# midi-thru_v1.net
KiCad netlist of a schematic drawn in EAGLE
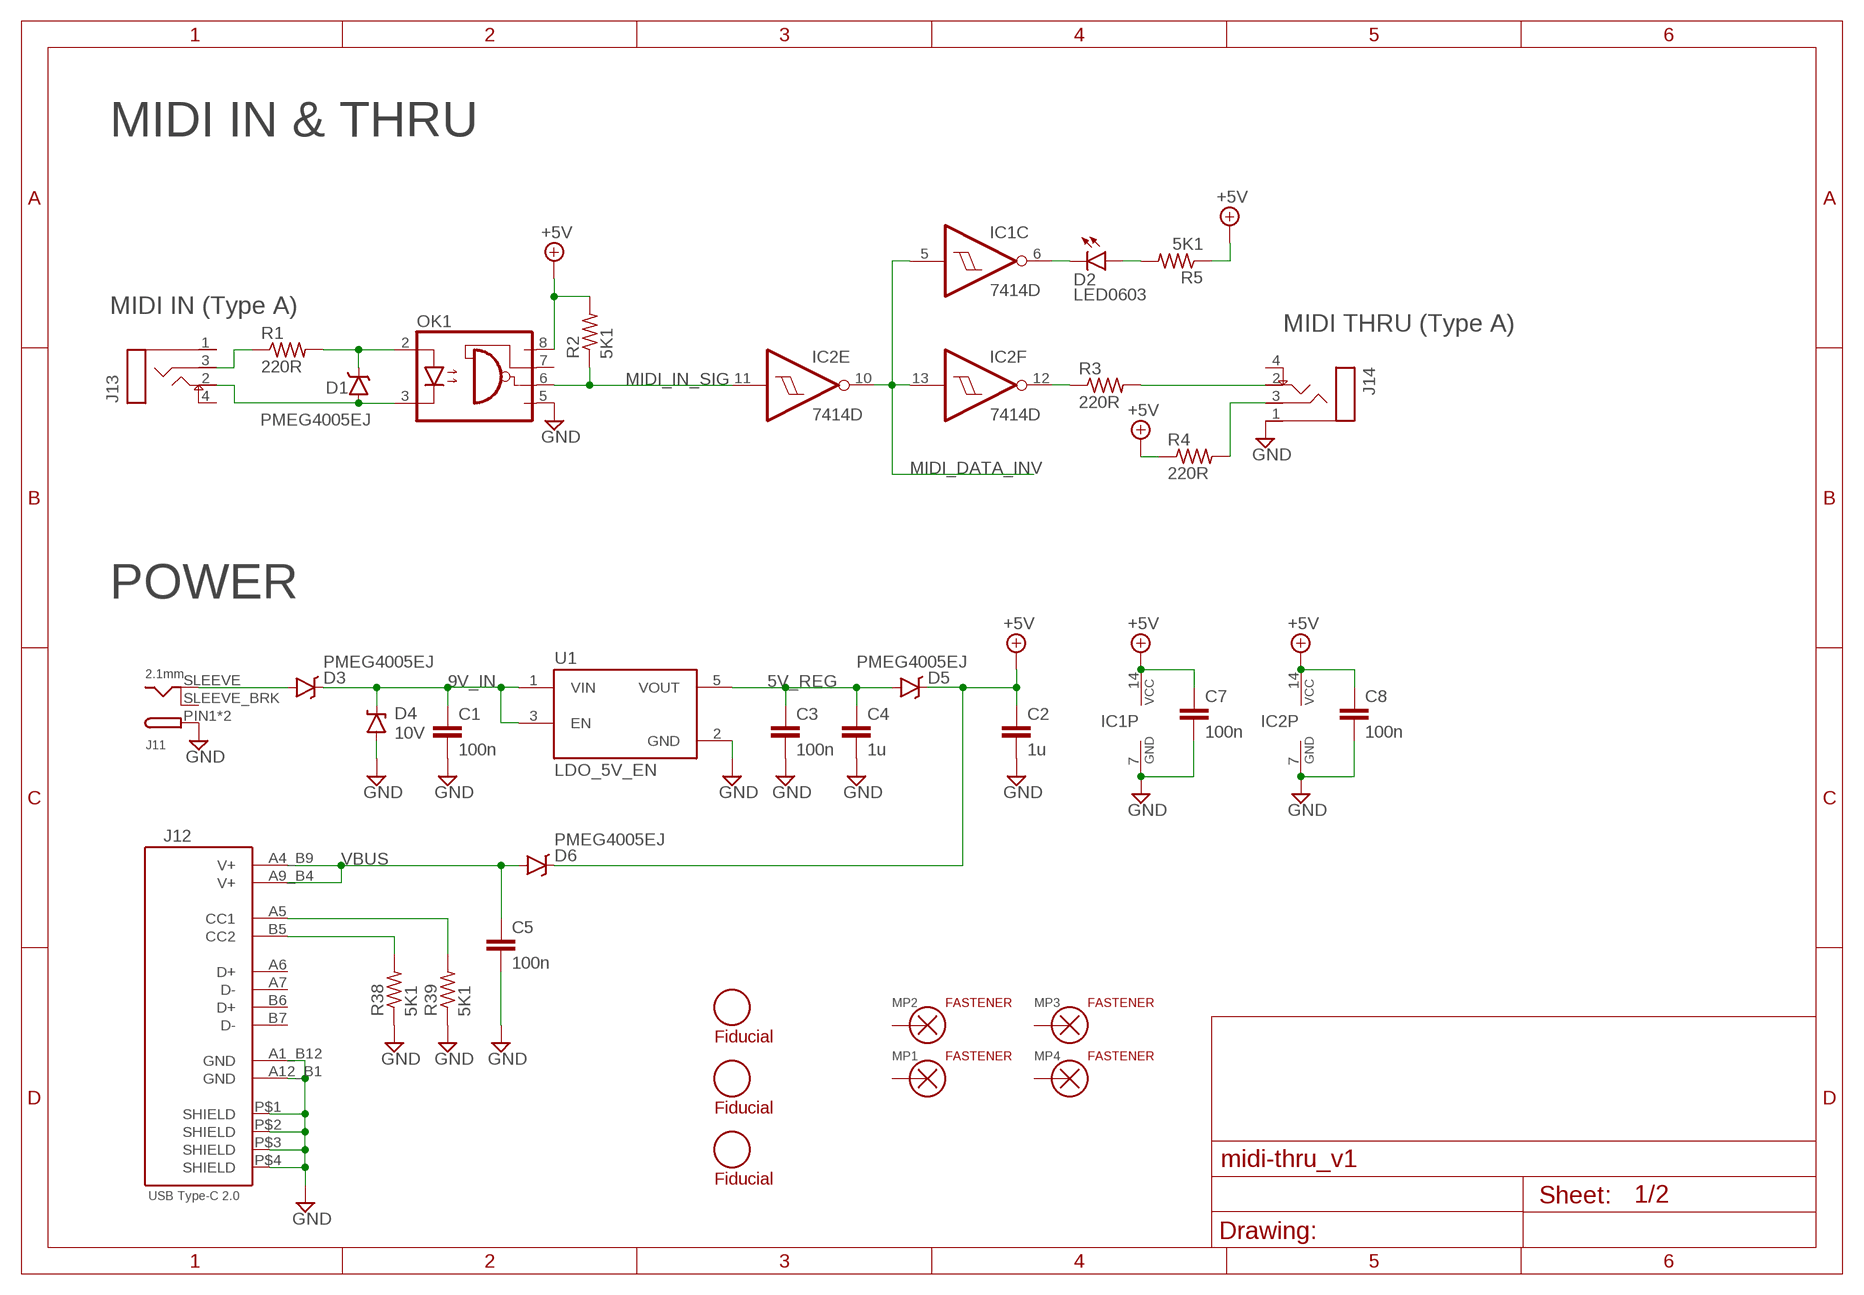
[diagram p0: schematic, sheet 1]
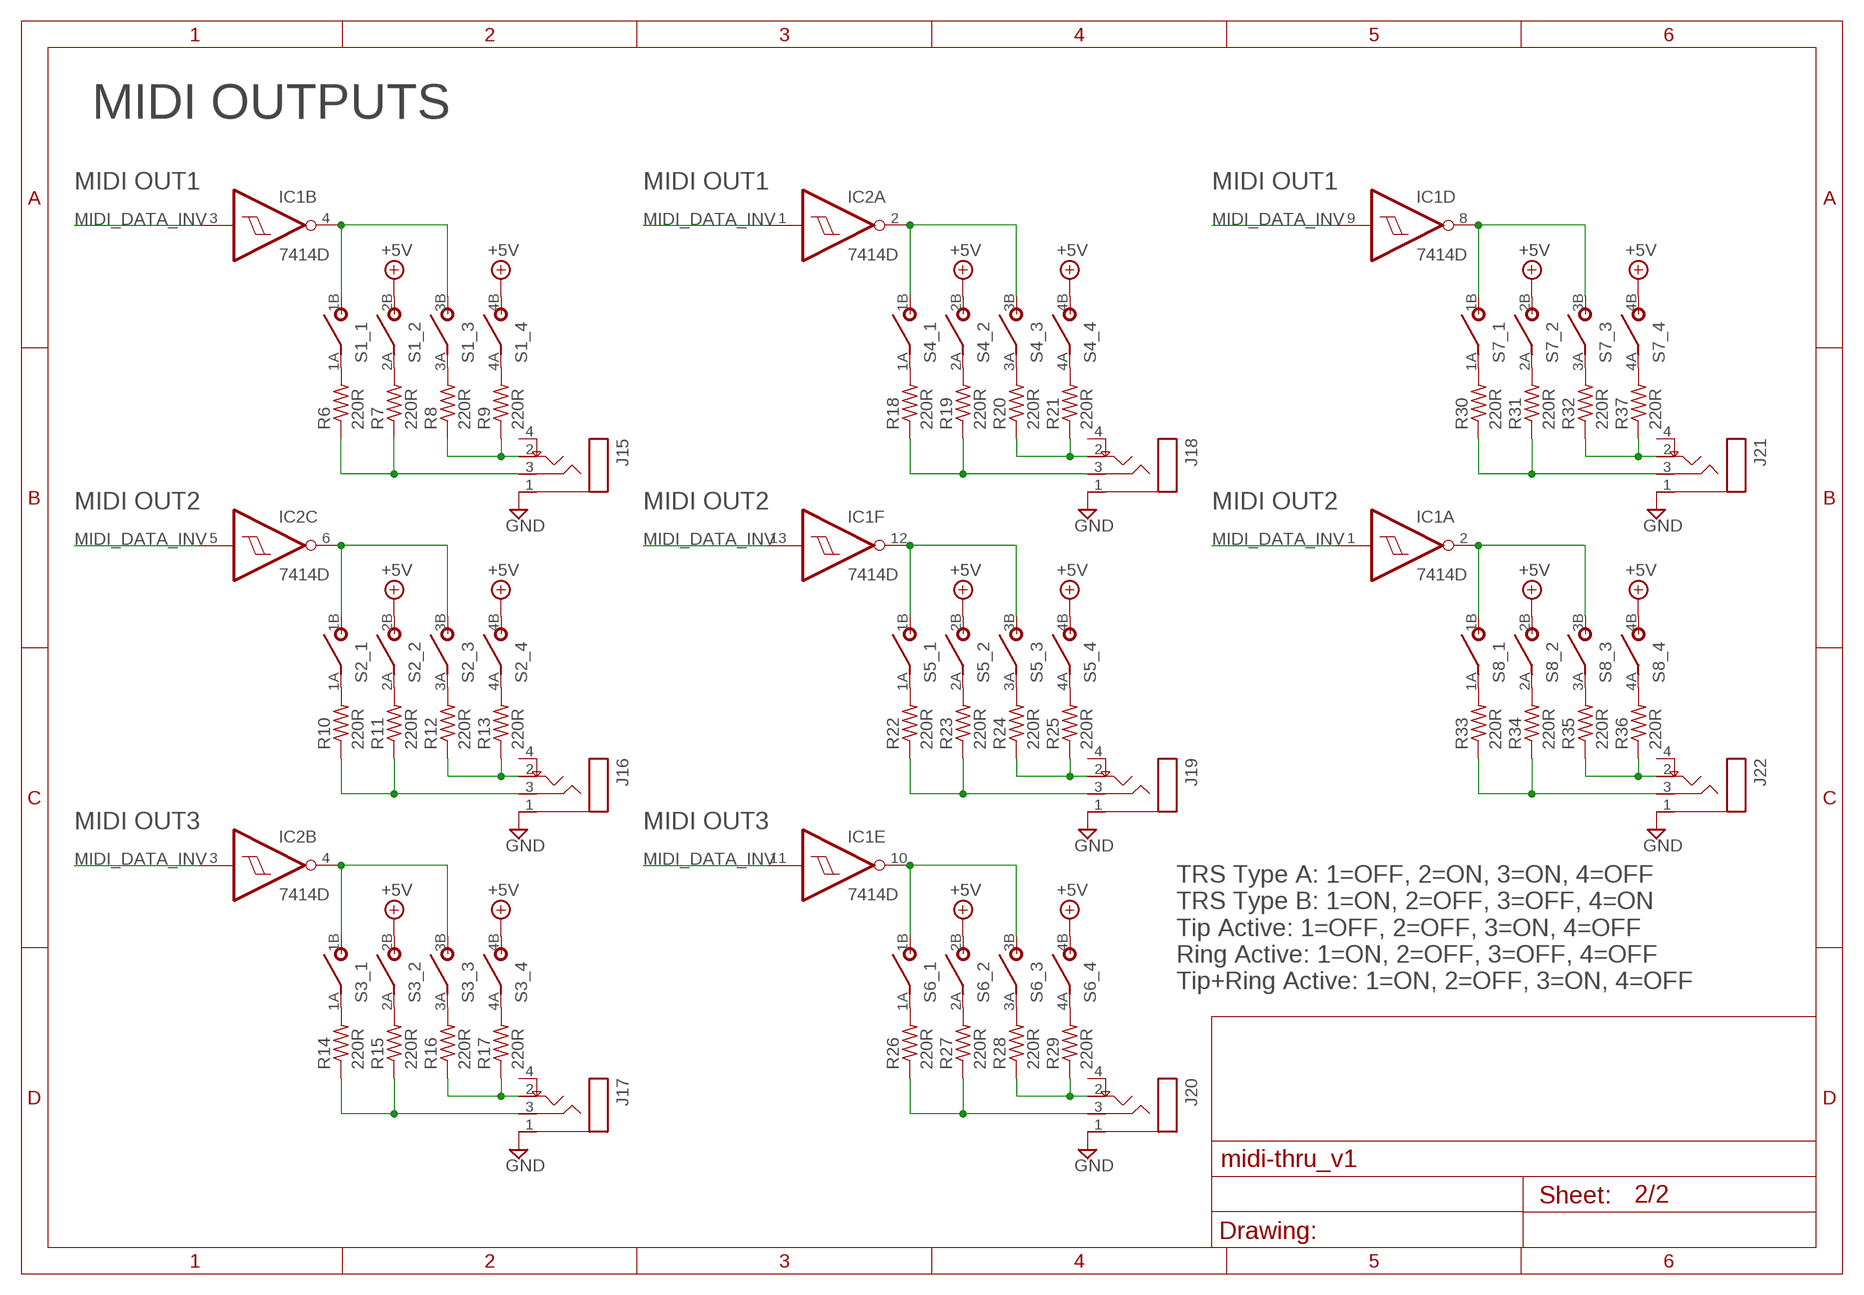
[diagram p1: schematic, sheet 2]

(export (version "E")
  (design (tool "Eeschema 10.0.6"))
  (components
    (comp (ref "IC1")
      (value "7414D")
      (footprint "eagle-import:SO14")
      (fields (field (name "MPN") "74HC14M/TR") (field (name "PART_NO") "74HC14-SOIC-14"))
      (libsource (lib "eagle-import") (part "7414D"))
    )
    (comp (ref "IC2")
      (value "7414D")
      (footprint "eagle-import:SO14")
      (fields (field (name "MPN") "74HC14M/TR") (field (name "PART_NO") "74HC14-SOIC-14"))
      (libsource (lib "eagle-import") (part "7414D"))
    )
    (comp (ref "J15")
      (value "TRS-TIP-SW")
      (footprint "eagle-import:PJ-327C-4A")
      (fields (field (name "MPN") "PJ-327C-4A"))
      (libsource (lib "eagle-import") (part "TRS-TIP-SW3.5MM1"))
    )
    (comp (ref "J16")
      (value "TRS-TIP-SW")
      (footprint "eagle-import:PJ-327C-4A")
      (fields (field (name "MPN") "PJ-327C-4A"))
      (libsource (lib "eagle-import") (part "TRS-TIP-SW3.5MM1"))
    )
    (comp (ref "J17")
      (value "TRS-TIP-SW")
      (footprint "eagle-import:PJ-327C-4A")
      (fields (field (name "MPN") "PJ-327C-4A"))
      (libsource (lib "eagle-import") (part "TRS-TIP-SW3.5MM1"))
    )
    (comp (ref "J18")
      (value "TRS-TIP-SW")
      (footprint "eagle-import:PJ-327C-4A")
      (fields (field (name "MPN") "PJ-327C-4A"))
      (libsource (lib "eagle-import") (part "TRS-TIP-SW3.5MM1"))
    )
    (comp (ref "J19")
      (value "TRS-TIP-SW")
      (footprint "eagle-import:PJ-327C-4A")
      (fields (field (name "MPN") "PJ-327C-4A"))
      (libsource (lib "eagle-import") (part "TRS-TIP-SW3.5MM1"))
    )
    (comp (ref "J20")
      (value "TRS-TIP-SW3.5MM1")
      (footprint "eagle-import:PJ-327C-4A")
      (fields (field (name "MPN") "PJ-327C-4A"))
      (libsource (lib "eagle-import") (part "TRS-TIP-SW3.5MM1"))
    )
    (comp (ref "J21")
      (value "TRS-TIP-SW3.5MM1")
      (footprint "eagle-import:PJ-327C-4A")
      (fields (field (name "MPN") "PJ-327C-4A"))
      (libsource (lib "eagle-import") (part "TRS-TIP-SW3.5MM1"))
    )
    (comp (ref "J22")
      (value "TRS-TIP-SW")
      (footprint "eagle-import:PJ-327C-4A")
      (fields (field (name "MPN") "PJ-327C-4A"))
      (libsource (lib "eagle-import") (part "TRS-TIP-SW3.5MM1"))
    )
    (comp (ref "R6")
      (value "220R")
      (footprint "eagle-import:0603-RES")
      (fields (field (name "MANUFACTURER") "YAGEO") (field (name "PART_NO") "R0603-220R"))
      (libsource (lib "eagle-import") (part "USR0603-220R"))
    )
    (comp (ref "R7")
      (value "220R")
      (footprint "eagle-import:0603-RES")
      (fields (field (name "MANUFACTURER") "YAGEO") (field (name "PART_NO") "R0603-220R"))
      (libsource (lib "eagle-import") (part "USR0603-220R"))
    )
    (comp (ref "R8")
      (value "220R")
      (footprint "eagle-import:0603-RES")
      (fields (field (name "MANUFACTURER") "YAGEO") (field (name "PART_NO") "R0603-220R"))
      (libsource (lib "eagle-import") (part "USR0603-220R"))
    )
    (comp (ref "R9")
      (value "220R")
      (footprint "eagle-import:0603-RES")
      (fields (field (name "MANUFACTURER") "YAGEO") (field (name "PART_NO") "R0603-220R"))
      (libsource (lib "eagle-import") (part "USR0603-220R"))
    )
    (comp (ref "R10")
      (value "220R")
      (footprint "eagle-import:0603-RES")
      (fields (field (name "MANUFACTURER") "YAGEO") (field (name "PART_NO") "R0603-220R"))
      (libsource (lib "eagle-import") (part "USR0603-220R"))
    )
    (comp (ref "R11")
      (value "220R")
      (footprint "eagle-import:0603-RES")
      (fields (field (name "MANUFACTURER") "YAGEO") (field (name "PART_NO") "R0603-220R"))
      (libsource (lib "eagle-import") (part "USR0603-220R"))
    )
    (comp (ref "R12")
      (value "220R")
      (footprint "eagle-import:0603-RES")
      (fields (field (name "MANUFACTURER") "YAGEO") (field (name "PART_NO") "R0603-220R"))
      (libsource (lib "eagle-import") (part "USR0603-220R"))
    )
    (comp (ref "R13")
      (value "220R")
      (footprint "eagle-import:0603-RES")
      (fields (field (name "MANUFACTURER") "YAGEO") (field (name "PART_NO") "R0603-220R"))
      (libsource (lib "eagle-import") (part "USR0603-220R"))
    )
    (comp (ref "R14")
      (value "220R")
      (footprint "eagle-import:0603-RES")
      (fields (field (name "MANUFACTURER") "YAGEO") (field (name "PART_NO") "R0603-220R"))
      (libsource (lib "eagle-import") (part "USR0603-220R"))
    )
    (comp (ref "R15")
      (value "220R")
      (footprint "eagle-import:0603-RES")
      (fields (field (name "MANUFACTURER") "YAGEO") (field (name "PART_NO") "R0603-220R"))
      (libsource (lib "eagle-import") (part "USR0603-220R"))
    )
    (comp (ref "R16")
      (value "220R")
      (footprint "eagle-import:0603-RES")
      (fields (field (name "MANUFACTURER") "YAGEO") (field (name "PART_NO") "R0603-220R"))
      (libsource (lib "eagle-import") (part "USR0603-220R"))
    )
    (comp (ref "R17")
      (value "220R")
      (footprint "eagle-import:0603-RES")
      (fields (field (name "MANUFACTURER") "YAGEO") (field (name "PART_NO") "R0603-220R"))
      (libsource (lib "eagle-import") (part "USR0603-220R"))
    )
    (comp (ref "R18")
      (value "220R")
      (footprint "eagle-import:0603-RES")
      (fields (field (name "MANUFACTURER") "YAGEO") (field (name "PART_NO") "R0603-220R"))
      (libsource (lib "eagle-import") (part "USR0603-220R"))
    )
    (comp (ref "R19")
      (value "220R")
      (footprint "eagle-import:0603-RES")
      (fields (field (name "MANUFACTURER") "YAGEO") (field (name "PART_NO") "R0603-220R"))
      (libsource (lib "eagle-import") (part "USR0603-220R"))
    )
    (comp (ref "R20")
      (value "220R")
      (footprint "eagle-import:0603-RES")
      (fields (field (name "MANUFACTURER") "YAGEO") (field (name "PART_NO") "R0603-220R"))
      (libsource (lib "eagle-import") (part "USR0603-220R"))
    )
    (comp (ref "R21")
      (value "220R")
      (footprint "eagle-import:0603-RES")
      (fields (field (name "MANUFACTURER") "YAGEO") (field (name "PART_NO") "R0603-220R"))
      (libsource (lib "eagle-import") (part "USR0603-220R"))
    )
    (comp (ref "R22")
      (value "220R")
      (footprint "eagle-import:0603-RES")
      (fields (field (name "MANUFACTURER") "YAGEO") (field (name "PART_NO") "R0603-220R"))
      (libsource (lib "eagle-import") (part "USR0603-220R"))
    )
    (comp (ref "R23")
      (value "220R")
      (footprint "eagle-import:0603-RES")
      (fields (field (name "MANUFACTURER") "YAGEO") (field (name "PART_NO") "R0603-220R"))
      (libsource (lib "eagle-import") (part "USR0603-220R"))
    )
    (comp (ref "R24")
      (value "220R")
      (footprint "eagle-import:0603-RES")
      (fields (field (name "MANUFACTURER") "YAGEO") (field (name "PART_NO") "R0603-220R"))
      (libsource (lib "eagle-import") (part "USR0603-220R"))
    )
    (comp (ref "R25")
      (value "220R")
      (footprint "eagle-import:0603-RES")
      (fields (field (name "MANUFACTURER") "YAGEO") (field (name "PART_NO") "R0603-220R"))
      (libsource (lib "eagle-import") (part "USR0603-220R"))
    )
    (comp (ref "R26")
      (value "220R")
      (footprint "eagle-import:0603-RES")
      (fields (field (name "MANUFACTURER") "YAGEO") (field (name "PART_NO") "R0603-220R"))
      (libsource (lib "eagle-import") (part "USR0603-220R"))
    )
    (comp (ref "R27")
      (value "220R")
      (footprint "eagle-import:0603-RES")
      (fields (field (name "MANUFACTURER") "YAGEO") (field (name "PART_NO") "R0603-220R"))
      (libsource (lib "eagle-import") (part "USR0603-220R"))
    )
    (comp (ref "R28")
      (value "220R")
      (footprint "eagle-import:0603-RES")
      (fields (field (name "MANUFACTURER") "YAGEO") (field (name "PART_NO") "R0603-220R"))
      (libsource (lib "eagle-import") (part "USR0603-220R"))
    )
    (comp (ref "R29")
      (value "220R")
      (footprint "eagle-import:0603-RES")
      (fields (field (name "MANUFACTURER") "YAGEO") (field (name "PART_NO") "R0603-220R"))
      (libsource (lib "eagle-import") (part "USR0603-220R"))
    )
    (comp (ref "R30")
      (value "220R")
      (footprint "eagle-import:0603-RES")
      (fields (field (name "MANUFACTURER") "YAGEO") (field (name "PART_NO") "R0603-220R"))
      (libsource (lib "eagle-import") (part "USR0603-220R"))
    )
    (comp (ref "R31")
      (value "220R")
      (footprint "eagle-import:0603-RES")
      (fields (field (name "MANUFACTURER") "YAGEO") (field (name "PART_NO") "R0603-220R"))
      (libsource (lib "eagle-import") (part "USR0603-220R"))
    )
    (comp (ref "R32")
      (value "220R")
      (footprint "eagle-import:0603-RES")
      (fields (field (name "MANUFACTURER") "YAGEO") (field (name "PART_NO") "R0603-220R"))
      (libsource (lib "eagle-import") (part "USR0603-220R"))
    )
    (comp (ref "R33")
      (value "220R")
      (footprint "eagle-import:0603-RES")
      (fields (field (name "MANUFACTURER") "YAGEO") (field (name "PART_NO") "R0603-220R"))
      (libsource (lib "eagle-import") (part "USR0603-220R"))
    )
    (comp (ref "R34")
      (value "220R")
      (footprint "eagle-import:0603-RES")
      (fields (field (name "MANUFACTURER") "YAGEO") (field (name "PART_NO") "R0603-220R"))
      (libsource (lib "eagle-import") (part "USR0603-220R"))
    )
    (comp (ref "R35")
      (value "220R")
      (footprint "eagle-import:0603-RES")
      (fields (field (name "MANUFACTURER") "YAGEO") (field (name "PART_NO") "R0603-220R"))
      (libsource (lib "eagle-import") (part "USR0603-220R"))
    )
    (comp (ref "R36")
      (value "220R")
      (footprint "eagle-import:0603-RES")
      (fields (field (name "MANUFACTURER") "YAGEO") (field (name "PART_NO") "R0603-220R"))
      (libsource (lib "eagle-import") (part "USR0603-220R"))
    )
    (comp (ref "R37")
      (value "220R")
      (footprint "eagle-import:0603-RES")
      (fields (field (name "MANUFACTURER") "YAGEO") (field (name "PART_NO") "R0603-220R"))
      (libsource (lib "eagle-import") (part "USR0603-220R"))
    )
    (comp (ref "S1")
      (value "DIPSW_4SMD")
      (footprint "eagle-import:DIP4_2.54")
      (fields
        (field (name "MANUFACTURER") "CUI")
        (field (name "MPN") "DS04-254-2-04BK-SMT")
        (field (name "PART_NO") "DIP4-2.54-SMD")
      )
      (libsource (lib "eagle-import") (part "DIPSW_4SMD"))
    )
    (comp (ref "S2")
      (value "DIPSW_4SMD")
      (footprint "eagle-import:DIP4_2.54")
      (fields
        (field (name "MANUFACTURER") "CUI")
        (field (name "MPN") "DS04-254-2-04BK-SMT")
        (field (name "PART_NO") "DIP4-2.54-SMD")
      )
      (libsource (lib "eagle-import") (part "DIPSW_4SMD"))
    )
    (comp (ref "S3")
      (value "DIPSW_4SMD")
      (footprint "eagle-import:DIP4_2.54")
      (fields
        (field (name "MANUFACTURER") "CUI")
        (field (name "MPN") "DS04-254-2-04BK-SMT")
        (field (name "PART_NO") "DIP4-2.54-SMD")
      )
      (libsource (lib "eagle-import") (part "DIPSW_4SMD"))
    )
    (comp (ref "S4")
      (value "DIPSW_4SMD")
      (footprint "eagle-import:DIP4_2.54")
      (fields
        (field (name "MANUFACTURER") "CUI")
        (field (name "MPN") "DS04-254-2-04BK-SMT")
        (field (name "PART_NO") "DIP4-2.54-SMD")
      )
      (libsource (lib "eagle-import") (part "DIPSW_4SMD"))
    )
    (comp (ref "S5")
      (value "DIPSW_4SMD")
      (footprint "eagle-import:DIP4_2.54")
      (fields
        (field (name "MANUFACTURER") "CUI")
        (field (name "MPN") "DS04-254-2-04BK-SMT")
        (field (name "PART_NO") "DIP4-2.54-SMD")
      )
      (libsource (lib "eagle-import") (part "DIPSW_4SMD"))
    )
    (comp (ref "S6")
      (value "DIPSW_4SMD")
      (footprint "eagle-import:DIP4_2.54")
      (fields
        (field (name "MANUFACTURER") "CUI")
        (field (name "MPN") "DS04-254-2-04BK-SMT")
        (field (name "PART_NO") "DIP4-2.54-SMD")
      )
      (libsource (lib "eagle-import") (part "DIPSW_4SMD"))
    )
    (comp (ref "S7")
      (value "DIPSW_4SMD")
      (footprint "eagle-import:DIP4_2.54")
      (fields
        (field (name "MANUFACTURER") "CUI")
        (field (name "MPN") "DS04-254-2-04BK-SMT")
        (field (name "PART_NO") "DIP4-2.54-SMD")
      )
      (libsource (lib "eagle-import") (part "DIPSW_4SMD"))
    )
    (comp (ref "S8")
      (value "DIPSW_4SMD")
      (footprint "eagle-import:DIP4_2.54")
      (fields
        (field (name "MANUFACTURER") "CUI")
        (field (name "MPN") "DS04-254-2-04BK-SMT")
        (field (name "PART_NO") "DIP4-2.54-SMD")
      )
      (libsource (lib "eagle-import") (part "DIPSW_4SMD"))
    )
    (comp (ref "C1")
      (value "100n")
      (footprint "eagle-import:0603_CAP")
      (fields
        (field (name "MANUFACTURER") "YAGEO")
        (field (name "PART_NO") "C0603-100NF-50V")
        (field (name "TOLERANCE") "10%")
      )
      (libsource (lib "eagle-import") (part "SMD-NPC0603-100N-50V"))
    )
    (comp (ref "C2")
      (value "1u")
      (footprint "eagle-import:0603_CAP")
      (fields
        (field (name "MANUFACTURER") "YAGEO")
        (field (name "PART_NO") "C0603-1UF-50V")
        (field (name "TOLERANCE") "10%")
      )
      (libsource (lib "eagle-import") (part "SMD-NPC0603-1U-50V"))
    )
    (comp (ref "C3")
      (value "100n")
      (footprint "eagle-import:0603_CAP")
      (fields
        (field (name "MANUFACTURER") "YAGEO")
        (field (name "PART_NO") "C0603-100NF-50V")
        (field (name "TOLERANCE") "10%")
      )
      (libsource (lib "eagle-import") (part "SMD-NPC0603-100N-50V"))
    )
    (comp (ref "C4")
      (value "1u")
      (footprint "eagle-import:0603_CAP")
      (fields
        (field (name "MANUFACTURER") "YAGEO")
        (field (name "PART_NO") "C0603-1UF-50V")
        (field (name "TOLERANCE") "10%")
      )
      (libsource (lib "eagle-import") (part "SMD-NPC0603-1U-50V"))
    )
    (comp (ref "C5")
      (value "100n")
      (footprint "eagle-import:0603_CAP")
      (fields
        (field (name "MANUFACTURER") "YAGEO")
        (field (name "PART_NO") "C0603-100NF-50V")
        (field (name "TOLERANCE") "10%")
      )
      (libsource (lib "eagle-import") (part "SMD-NPC0603-100N-50V"))
    )
    (comp (ref "C7")
      (value "100n")
      (footprint "eagle-import:0603_CAP")
      (fields
        (field (name "MANUFACTURER") "YAGEO")
        (field (name "PART_NO") "C0603-100NF-50V")
        (field (name "TOLERANCE") "10%")
      )
      (libsource (lib "eagle-import") (part "SMD-NPC0603-100N-50V"))
    )
    (comp (ref "C8")
      (value "100n")
      (footprint "eagle-import:0603_CAP")
      (fields
        (field (name "MANUFACTURER") "YAGEO")
        (field (name "PART_NO") "C0603-100NF-50V")
        (field (name "TOLERANCE") "10%")
      )
      (libsource (lib "eagle-import") (part "SMD-NPC0603-100N-50V"))
    )
    (comp (ref "D1")
      (value "PMEG4005EJ")
      (footprint "eagle-import:SOD-323")
      (fields (field (name "PART_NO") "SOD323-SCHOTTKY-1A"))
      (libsource (lib "eagle-import") (part "DIODE-SCHOTTKY-PMEG4005EJ"))
    )
    (comp (ref "D2")
      (value "LED0603")
      (footprint "eagle-import:CHIPLED_0603")
      (fields (field (name "PART_NO") "LED-0603-RED"))
      (libsource (lib "eagle-import") (part "LED0603_R"))
    )
    (comp (ref "D3")
      (value "PMEG4005EJ")
      (footprint "eagle-import:SOD-323")
      (fields (field (name "PART_NO") "SOD323-SCHOTTKY-1A"))
      (libsource (lib "eagle-import") (part "DIODE-SCHOTTKY-PMEG4005EJ"))
    )
    (comp (ref "D4")
      (value "10V")
      (footprint "eagle-import:SOD-323")
      (fields (field (name "PART_NO") "MM3Z10VST1G"))
      (libsource (lib "eagle-import") (part "DIODE-ZENER10V"))
    )
    (comp (ref "D5")
      (value "PMEG4005EJ")
      (footprint "eagle-import:SOD-323")
      (fields (field (name "PART_NO") "SOD323-SCHOTTKY-1A"))
      (libsource (lib "eagle-import") (part "DIODE-SCHOTTKY-PMEG4005EJ"))
    )
    (comp (ref "D6")
      (value "PMEG4005EJ")
      (footprint "eagle-import:SOD-323")
      (fields (field (name "PART_NO") "SOD323-SCHOTTKY-1A"))
      (libsource (lib "eagle-import") (part "DIODE-SCHOTTKY-PMEG4005EJ"))
    )
    (comp (ref "FD1")
      (value "FIDUCIALROUND_1MM")
      (footprint "eagle-import:FIDUCIAL_ROUND_1MM")
      (libsource (lib "eagle-import") (part "FIDUCIALROUND_1MM"))
    )
    (comp (ref "FD2")
      (value "FIDUCIALROUND_1MM")
      (footprint "eagle-import:FIDUCIAL_ROUND_1MM")
      (libsource (lib "eagle-import") (part "FIDUCIALROUND_1MM"))
    )
    (comp (ref "FD3")
      (value "FIDUCIALROUND_1MM")
      (footprint "eagle-import:FIDUCIAL_ROUND_1MM")
      (libsource (lib "eagle-import") (part "FIDUCIALROUND_1MM"))
    )
    (comp (ref "J11")
      (value "2.1mm")
      (footprint "eagle-import:DCJACK_2MM_SMT")
      (fields
        (field (name "MANUFACTURER") "TENSILITY INTERNATIONAL CORP")
        (field (name "MPN") "54-00164")
        (field (name "PART_NO") "DC-2.1-SMD")
      )
      (libsource (lib "eagle-import") (part "DCSMT"))
    )
    (comp (ref "J12")
      (value "USB_TYPE-C_2.0")
      (footprint "eagle-import:12402012E212A")
      (fields
        (field (name "MANUFACTURER") "AMPHENOL")
        (field (name "MPN") "12402012E212A")
        (field (name "PART_NO") "USBC-2.0")
      )
      (libsource (lib "eagle-import") (part "USB_TYPE-C_2.0"))
    )
    (comp (ref "J13")
      (value "TRS-TIP-SW3.5MM1")
      (footprint "eagle-import:PJ-327C-4A")
      (fields (field (name "MPN") "PJ-327C-4A"))
      (libsource (lib "eagle-import") (part "TRS-TIP-SW3.5MM1"))
    )
    (comp (ref "J14")
      (value "TRS-TIP-SW3.5MM1")
      (footprint "eagle-import:PJ-327C-4A")
      (fields (field (name "MPN") "PJ-327C-4A"))
      (libsource (lib "eagle-import") (part "TRS-TIP-SW3.5MM1"))
    )
    (comp (ref "MP1")
      (value "SCREW-FASTENER3")
      (footprint "eagle-import:M3-PANHEAD-VIA")
      (libsource (lib "eagle-import") (part "SCREW-FASTENER3"))
    )
    (comp (ref "MP2")
      (value "SCREW-FASTENER3")
      (footprint "eagle-import:M3-PANHEAD-VIA")
      (libsource (lib "eagle-import") (part "SCREW-FASTENER3"))
    )
    (comp (ref "MP3")
      (value "SCREW-FASTENER3")
      (footprint "eagle-import:M3-PANHEAD-VIA")
      (libsource (lib "eagle-import") (part "SCREW-FASTENER3"))
    )
    (comp (ref "MP4")
      (value "SCREW-FASTENER3")
      (footprint "eagle-import:M3-PANHEAD-VIA")
      (libsource (lib "eagle-import") (part "SCREW-FASTENER3"))
    )
    (comp (ref "OK1")
      (value "6N137")
      (footprint "eagle-import:SMD8")
      (fields
        (field (name "MANUFACTURER") "LITE-ON")
        (field (name "MPN") "6N137S")
        (field (name "PART_NO") "6N137-SMD")
      )
      (libsource (lib "eagle-import") (part "6N137S"))
    )
    (comp (ref "R1")
      (value "220R")
      (footprint "eagle-import:0603-RES")
      (fields (field (name "MANUFACTURER") "YAGEO") (field (name "PART_NO") "R0603-220R"))
      (libsource (lib "eagle-import") (part "USR0603-220R"))
    )
    (comp (ref "R2")
      (value "5K1")
      (footprint "eagle-import:0603-RES")
      (fields (field (name "MANUFACTURER") "YAGEO") (field (name "PART_NO") "R0603-5K1"))
      (libsource (lib "eagle-import") (part "USR0603-5K1"))
    )
    (comp (ref "R3")
      (value "220R")
      (footprint "eagle-import:0603-RES")
      (fields (field (name "MANUFACTURER") "YAGEO") (field (name "PART_NO") "R0603-220R"))
      (libsource (lib "eagle-import") (part "USR0603-220R"))
    )
    (comp (ref "R4")
      (value "220R")
      (footprint "eagle-import:0603-RES")
      (fields (field (name "MANUFACTURER") "YAGEO") (field (name "PART_NO") "R0603-220R"))
      (libsource (lib "eagle-import") (part "USR0603-220R"))
    )
    (comp (ref "R5")
      (value "5K1")
      (footprint "eagle-import:0603-RES")
      (fields (field (name "MANUFACTURER") "YAGEO") (field (name "PART_NO") "R0603-5K1"))
      (libsource (lib "eagle-import") (part "USR0603-5K1"))
    )
    (comp (ref "R38")
      (value "5K1")
      (footprint "eagle-import:0603-RES")
      (fields (field (name "MANUFACTURER") "YAGEO") (field (name "PART_NO") "R0603-5K1"))
      (libsource (lib "eagle-import") (part "USR0603-5K1"))
    )
    (comp (ref "R39")
      (value "5K1")
      (footprint "eagle-import:0603-RES")
      (fields (field (name "MANUFACTURER") "YAGEO") (field (name "PART_NO") "R0603-5K1"))
      (libsource (lib "eagle-import") (part "USR0603-5K1"))
    )
    (comp (ref "U1")
      (value "LDO_5V_EN")
      (footprint "eagle-import:SOT23-5")
      (fields (field (name "MPN") "SPX5205M5-L-5-0/TR") (field (name "PART_NO") "LDO-SOT23-5V"))
      (libsource (lib "eagle-import") (part "LDO_5V_EN"))
    )
  )
  (nets
    (net (code "1") (name "+5V") (class "Default")
      (node (ref "C2") (pin "1") (pinfunction "1_1") (pintype "passive"))
      (node (ref "C7") (pin "1") (pinfunction "1_1") (pintype "passive"))
      (node (ref "C8") (pin "1") (pinfunction "1_1") (pintype "passive"))
      (node (ref "D5") (pin "C") (pinfunction "C_C") (pintype "passive"))
      (node (ref "D6") (pin "C") (pinfunction "C_C") (pintype "passive"))
      (node (ref "IC1") (pin "14") (pinfunction "VCC_14") (pintype "power_in"))
      (node (ref "IC2") (pin "14") (pinfunction "VCC_14") (pintype "power_in"))
      (node (ref "OK1") (pin "8") (pinfunction "VCC_8") (pintype "passive"))
      (node (ref "R2") (pin "2") (pinfunction "2_2") (pintype "passive"))
      (node (ref "R4") (pin "1") (pinfunction "1_1") (pintype "passive"))
      (node (ref "R5") (pin "1") (pinfunction "1_1") (pintype "passive"))
      (node (ref "S1") (pin "2B") (pinfunction "S_2B") (pintype "passive"))
      (node (ref "S1") (pin "4B") (pinfunction "S_4B") (pintype "passive"))
      (node (ref "S2") (pin "2B") (pinfunction "S_2B") (pintype "passive"))
      (node (ref "S2") (pin "4B") (pinfunction "S_4B") (pintype "passive"))
      (node (ref "S3") (pin "2B") (pinfunction "S_2B") (pintype "passive"))
      (node (ref "S3") (pin "4B") (pinfunction "S_4B") (pintype "passive"))
      (node (ref "S4") (pin "2B") (pinfunction "S_2B") (pintype "passive"))
      (node (ref "S4") (pin "4B") (pinfunction "S_4B") (pintype "passive"))
      (node (ref "S5") (pin "2B") (pinfunction "S_2B") (pintype "passive"))
      (node (ref "S5") (pin "4B") (pinfunction "S_4B") (pintype "passive"))
      (node (ref "S6") (pin "2B") (pinfunction "S_2B") (pintype "passive"))
      (node (ref "S6") (pin "4B") (pinfunction "S_4B") (pintype "passive"))
      (node (ref "S7") (pin "2B") (pinfunction "S_2B") (pintype "passive"))
      (node (ref "S7") (pin "4B") (pinfunction "S_4B") (pintype "passive"))
      (node (ref "S8") (pin "2B") (pinfunction "S_2B") (pintype "passive"))
      (node (ref "S8") (pin "4B") (pinfunction "S_4B") (pintype "passive"))
    )
    (net (code "2") (name "5V_REG") (class "Default")
      (node (ref "C3") (pin "1") (pinfunction "1_1") (pintype "passive"))
      (node (ref "C4") (pin "1") (pinfunction "1_1") (pintype "passive"))
      (node (ref "D5") (pin "A") (pinfunction "A_A") (pintype "passive"))
      (node (ref "U1") (pin "5") (pinfunction "VOUT_5") (pintype "output"))
    )
    (net (code "3") (name "9V_IN") (class "Default")
      (node (ref "C1") (pin "1") (pinfunction "1_1") (pintype "passive"))
      (node (ref "D3") (pin "C") (pinfunction "C_C") (pintype "passive"))
      (node (ref "D4") (pin "C") (pinfunction "C_C") (pintype "passive"))
      (node (ref "U1") (pin "1") (pinfunction "VIN_1") (pintype "input"))
      (node (ref "U1") (pin "3") (pinfunction "EN_3") (pintype "input"))
    )
    (net (code "4") (name "CONNECT") (class "Default")
      (node (ref "J11") (pin "SLEEVE_BRK") (pinfunction "CONNECT_SLEEVE_BRK") (pintype "power_in"))
    )
    (net (code "5") (name "GND") (class "Default")
      (node (ref "C1") (pin "2") (pinfunction "2_2") (pintype "passive"))
      (node (ref "C2") (pin "2") (pinfunction "2_2") (pintype "passive"))
      (node (ref "C3") (pin "2") (pinfunction "2_2") (pintype "passive"))
      (node (ref "C4") (pin "2") (pinfunction "2_2") (pintype "passive"))
      (node (ref "C5") (pin "2") (pinfunction "2_2") (pintype "passive"))
      (node (ref "C7") (pin "2") (pinfunction "2_2") (pintype "passive"))
      (node (ref "C8") (pin "2") (pinfunction "2_2") (pintype "passive"))
      (node (ref "D4") (pin "A") (pinfunction "A_A") (pintype "passive"))
      (node (ref "IC1") (pin "7") (pinfunction "GND_7") (pintype "power_in"))
      (node (ref "IC2") (pin "7") (pinfunction "GND_7") (pintype "power_in"))
      (node (ref "J11") (pin "PIN1") (pinfunction "PIN_PIN1") (pintype "power_in"))
      (node (ref "J11") (pin "PIN2") (pinfunction "PIN_PIN2") (pintype "power_in"))
      (node (ref "J12") (pin "A12_B1") (pinfunction "GND_A12_B1") (pintype "power_in"))
      (node (ref "J12") (pin "A1_B12") (pinfunction "GND_A1_B12") (pintype "power_in"))
      (node (ref "J12") (pin "P$1") (pinfunction "SHIELD_P$1") (pintype "bidirectional"))
      (node (ref "J12") (pin "P$2") (pinfunction "SHIELD_P$2") (pintype "bidirectional"))
      (node (ref "J12") (pin "P$3") (pinfunction "SHIELD_P$3") (pintype "bidirectional"))
      (node (ref "J12") (pin "P$4") (pinfunction "SHIELD_P$4") (pintype "bidirectional"))
      (node (ref "J14") (pin "1") (pinfunction "S_1") (pintype "passive"))
      (node (ref "J15") (pin "1") (pinfunction "S_1") (pintype "passive"))
      (node (ref "J16") (pin "1") (pinfunction "S_1") (pintype "passive"))
      (node (ref "J17") (pin "1") (pinfunction "S_1") (pintype "passive"))
      (node (ref "J18") (pin "1") (pinfunction "S_1") (pintype "passive"))
      (node (ref "J19") (pin "1") (pinfunction "S_1") (pintype "passive"))
      (node (ref "J20") (pin "1") (pinfunction "S_1") (pintype "passive"))
      (node (ref "J21") (pin "1") (pinfunction "S_1") (pintype "passive"))
      (node (ref "J22") (pin "1") (pinfunction "S_1") (pintype "passive"))
      (node (ref "OK1") (pin "5") (pinfunction "GND_5") (pintype "passive"))
      (node (ref "R38") (pin "1") (pinfunction "1_1") (pintype "passive"))
      (node (ref "R39") (pin "1") (pinfunction "1_1") (pintype "passive"))
      (node (ref "U1") (pin "2") (pinfunction "GND_2") (pintype "power_in"))
    )
    (net (code "6") (name "MIDI_DATA_INV") (class "Default")
      (node (ref "IC1") (pin "1") (pinfunction "I_1") (pintype "input"))
      (node (ref "IC1") (pin "11") (pinfunction "I_11") (pintype "input"))
      (node (ref "IC1") (pin "13") (pinfunction "I_13") (pintype "input"))
      (node (ref "IC1") (pin "3") (pinfunction "I_3") (pintype "input"))
      (node (ref "IC1") (pin "5") (pinfunction "I_5") (pintype "input"))
      (node (ref "IC1") (pin "9") (pinfunction "I_9") (pintype "input"))
      (node (ref "IC2") (pin "1") (pinfunction "I_1") (pintype "input"))
      (node (ref "IC2") (pin "10") (pinfunction "O_10") (pintype "output"))
      (node (ref "IC2") (pin "13") (pinfunction "I_13") (pintype "input"))
      (node (ref "IC2") (pin "3") (pinfunction "I_3") (pintype "input"))
      (node (ref "IC2") (pin "5") (pinfunction "I_5") (pintype "input"))
    )
    (net (code "7") (name "MIDI_IN_SIG") (class "Default")
      (node (ref "IC2") (pin "11") (pinfunction "I_11") (pintype "input"))
      (node (ref "OK1") (pin "6") (pinfunction "VO_6") (pintype "passive"))
      (node (ref "R2") (pin "1") (pinfunction "1_1") (pintype "passive"))
    )
    (net (code "8") (name "Net-(D2-PadA)") (class "Default")
      (node (ref "D2") (pin "A") (pinfunction "A_A") (pintype "passive"))
      (node (ref "R5") (pin "2") (pinfunction "2_2") (pintype "passive"))
    )
    (net (code "9") (name "Net-(D3-PadA)") (class "Default")
      (node (ref "D3") (pin "A") (pinfunction "A_A") (pintype "passive"))
      (node (ref "J11") (pin "SLEEVE") (pinfunction "SLEEVE_SLEEVE") (pintype "power_in"))
    )
    (net (code "10") (name "Net-(IC1A-O)") (class "Default")
      (node (ref "IC1") (pin "2") (pinfunction "O_2") (pintype "output"))
      (node (ref "S8") (pin "1B") (pinfunction "S_1B") (pintype "passive"))
      (node (ref "S8") (pin "3B") (pinfunction "S_3B") (pintype "passive"))
    )
    (net (code "11") (name "Net-(IC1B-O)") (class "Default")
      (node (ref "IC1") (pin "4") (pinfunction "O_4") (pintype "output"))
      (node (ref "S1") (pin "1B") (pinfunction "S_1B") (pintype "passive"))
      (node (ref "S1") (pin "3B") (pinfunction "S_3B") (pintype "passive"))
    )
    (net (code "12") (name "Net-(IC1C-O)") (class "Default")
      (node (ref "D2") (pin "C") (pinfunction "C_C") (pintype "passive"))
      (node (ref "IC1") (pin "6") (pinfunction "O_6") (pintype "output"))
    )
    (net (code "13") (name "Net-(IC1D-O)") (class "Default")
      (node (ref "IC1") (pin "8") (pinfunction "O_8") (pintype "output"))
      (node (ref "S7") (pin "1B") (pinfunction "S_1B") (pintype "passive"))
      (node (ref "S7") (pin "3B") (pinfunction "S_3B") (pintype "passive"))
    )
    (net (code "14") (name "Net-(IC1E-O)") (class "Default")
      (node (ref "IC1") (pin "10") (pinfunction "O_10") (pintype "output"))
      (node (ref "S6") (pin "1B") (pinfunction "S_1B") (pintype "passive"))
      (node (ref "S6") (pin "3B") (pinfunction "S_3B") (pintype "passive"))
    )
    (net (code "15") (name "Net-(IC1F-O)") (class "Default")
      (node (ref "IC1") (pin "12") (pinfunction "O_12") (pintype "output"))
      (node (ref "S5") (pin "1B") (pinfunction "S_1B") (pintype "passive"))
      (node (ref "S5") (pin "3B") (pinfunction "S_3B") (pintype "passive"))
    )
    (net (code "16") (name "Net-(IC2A-O)") (class "Default")
      (node (ref "IC2") (pin "2") (pinfunction "O_2") (pintype "output"))
      (node (ref "S4") (pin "1B") (pinfunction "S_1B") (pintype "passive"))
      (node (ref "S4") (pin "3B") (pinfunction "S_3B") (pintype "passive"))
    )
    (net (code "17") (name "Net-(IC2B-O)") (class "Default")
      (node (ref "IC2") (pin "4") (pinfunction "O_4") (pintype "output"))
      (node (ref "S3") (pin "1B") (pinfunction "S_1B") (pintype "passive"))
      (node (ref "S3") (pin "3B") (pinfunction "S_3B") (pintype "passive"))
    )
    (net (code "18") (name "Net-(IC2C-O)") (class "Default")
      (node (ref "IC2") (pin "6") (pinfunction "O_6") (pintype "output"))
      (node (ref "S2") (pin "1B") (pinfunction "S_1B") (pintype "passive"))
      (node (ref "S2") (pin "3B") (pinfunction "S_3B") (pintype "passive"))
    )
    (net (code "19") (name "Net-(IC2F-O)") (class "Default")
      (node (ref "IC2") (pin "12") (pinfunction "O_12") (pintype "output"))
      (node (ref "R3") (pin "1") (pinfunction "1_1") (pintype "passive"))
    )
    (net (code "20") (name "Net-(J12-CC1)") (class "Default")
      (node (ref "J12") (pin "A5") (pinfunction "CC1_A5") (pintype "bidirectional"))
      (node (ref "R39") (pin "2") (pinfunction "2_2") (pintype "passive"))
    )
    (net (code "21") (name "Net-(J12-CC2)") (class "Default")
      (node (ref "J12") (pin "B5") (pinfunction "CC2_B5") (pintype "bidirectional"))
      (node (ref "R38") (pin "2") (pinfunction "2_2") (pintype "passive"))
    )
    (net (code "22") (name "Net-(J13-R)") (class "Default")
      (node (ref "J13") (pin "3") (pinfunction "R_3") (pintype "passive"))
      (node (ref "R1") (pin "1") (pinfunction "1_1") (pintype "passive"))
    )
    (net (code "23") (name "Net-(J13-T)") (class "Default")
      (node (ref "D1") (pin "A") (pinfunction "A_A") (pintype "passive"))
      (node (ref "J13") (pin "2") (pinfunction "T_2") (pintype "passive"))
      (node (ref "OK1") (pin "3") (pinfunction "C_3") (pintype "passive"))
    )
    (net (code "24") (name "Net-(J14-R)") (class "Default")
      (node (ref "J14") (pin "3") (pinfunction "R_3") (pintype "passive"))
      (node (ref "R4") (pin "2") (pinfunction "2_2") (pintype "passive"))
    )
    (net (code "25") (name "Net-(J14-T)") (class "Default")
      (node (ref "J14") (pin "2") (pinfunction "T_2") (pintype "passive"))
      (node (ref "R3") (pin "2") (pinfunction "2_2") (pintype "passive"))
    )
    (net (code "26") (name "Net-(J15-R)") (class "Default")
      (node (ref "J15") (pin "3") (pinfunction "R_3") (pintype "passive"))
      (node (ref "R6") (pin "1") (pinfunction "1_1") (pintype "passive"))
      (node (ref "R7") (pin "1") (pinfunction "1_1") (pintype "passive"))
    )
    (net (code "27") (name "Net-(J15-T)") (class "Default")
      (node (ref "J15") (pin "2") (pinfunction "T_2") (pintype "passive"))
      (node (ref "R8") (pin "1") (pinfunction "1_1") (pintype "passive"))
      (node (ref "R9") (pin "1") (pinfunction "1_1") (pintype "passive"))
    )
    (net (code "28") (name "Net-(J16-R)") (class "Default")
      (node (ref "J16") (pin "3") (pinfunction "R_3") (pintype "passive"))
      (node (ref "R10") (pin "1") (pinfunction "1_1") (pintype "passive"))
      (node (ref "R11") (pin "1") (pinfunction "1_1") (pintype "passive"))
    )
    (net (code "29") (name "Net-(J16-T)") (class "Default")
      (node (ref "J16") (pin "2") (pinfunction "T_2") (pintype "passive"))
      (node (ref "R12") (pin "1") (pinfunction "1_1") (pintype "passive"))
      (node (ref "R13") (pin "1") (pinfunction "1_1") (pintype "passive"))
    )
    (net (code "30") (name "Net-(J17-R)") (class "Default")
      (node (ref "J17") (pin "3") (pinfunction "R_3") (pintype "passive"))
      (node (ref "R14") (pin "1") (pinfunction "1_1") (pintype "passive"))
      (node (ref "R15") (pin "1") (pinfunction "1_1") (pintype "passive"))
    )
    (net (code "31") (name "Net-(J17-T)") (class "Default")
      (node (ref "J17") (pin "2") (pinfunction "T_2") (pintype "passive"))
      (node (ref "R16") (pin "1") (pinfunction "1_1") (pintype "passive"))
      (node (ref "R17") (pin "1") (pinfunction "1_1") (pintype "passive"))
    )
    (net (code "32") (name "Net-(J18-R)") (class "Default")
      (node (ref "J18") (pin "3") (pinfunction "R_3") (pintype "passive"))
      (node (ref "R18") (pin "1") (pinfunction "1_1") (pintype "passive"))
      (node (ref "R19") (pin "1") (pinfunction "1_1") (pintype "passive"))
    )
    (net (code "33") (name "Net-(J18-T)") (class "Default")
      (node (ref "J18") (pin "2") (pinfunction "T_2") (pintype "passive"))
      (node (ref "R20") (pin "1") (pinfunction "1_1") (pintype "passive"))
      (node (ref "R21") (pin "1") (pinfunction "1_1") (pintype "passive"))
    )
    (net (code "34") (name "Net-(J19-R)") (class "Default")
      (node (ref "J19") (pin "3") (pinfunction "R_3") (pintype "passive"))
      (node (ref "R22") (pin "1") (pinfunction "1_1") (pintype "passive"))
      (node (ref "R23") (pin "1") (pinfunction "1_1") (pintype "passive"))
    )
    (net (code "35") (name "Net-(J19-T)") (class "Default")
      (node (ref "J19") (pin "2") (pinfunction "T_2") (pintype "passive"))
      (node (ref "R24") (pin "1") (pinfunction "1_1") (pintype "passive"))
      (node (ref "R25") (pin "1") (pinfunction "1_1") (pintype "passive"))
    )
    (net (code "36") (name "Net-(J20-R)") (class "Default")
      (node (ref "J20") (pin "3") (pinfunction "R_3") (pintype "passive"))
      (node (ref "R26") (pin "1") (pinfunction "1_1") (pintype "passive"))
      (node (ref "R27") (pin "1") (pinfunction "1_1") (pintype "passive"))
    )
    (net (code "37") (name "Net-(J20-T)") (class "Default")
      (node (ref "J20") (pin "2") (pinfunction "T_2") (pintype "passive"))
      (node (ref "R28") (pin "1") (pinfunction "1_1") (pintype "passive"))
      (node (ref "R29") (pin "1") (pinfunction "1_1") (pintype "passive"))
    )
    (net (code "38") (name "Net-(J21-R)") (class "Default")
      (node (ref "J21") (pin "3") (pinfunction "R_3") (pintype "passive"))
      (node (ref "R30") (pin "1") (pinfunction "1_1") (pintype "passive"))
      (node (ref "R31") (pin "1") (pinfunction "1_1") (pintype "passive"))
    )
    (net (code "39") (name "Net-(J21-T)") (class "Default")
      (node (ref "J21") (pin "2") (pinfunction "T_2") (pintype "passive"))
      (node (ref "R32") (pin "1") (pinfunction "1_1") (pintype "passive"))
      (node (ref "R37") (pin "1") (pinfunction "1_1") (pintype "passive"))
    )
    (net (code "40") (name "Net-(J22-R)") (class "Default")
      (node (ref "J22") (pin "3") (pinfunction "R_3") (pintype "passive"))
      (node (ref "R33") (pin "1") (pinfunction "1_1") (pintype "passive"))
      (node (ref "R34") (pin "1") (pinfunction "1_1") (pintype "passive"))
    )
    (net (code "41") (name "Net-(J22-T)") (class "Default")
      (node (ref "J22") (pin "2") (pinfunction "T_2") (pintype "passive"))
      (node (ref "R35") (pin "1") (pinfunction "1_1") (pintype "passive"))
      (node (ref "R36") (pin "1") (pinfunction "1_1") (pintype "passive"))
    )
    (net (code "42") (name "Net-(OK1-A)") (class "Default")
      (node (ref "D1") (pin "C") (pinfunction "C_C") (pintype "passive"))
      (node (ref "OK1") (pin "2") (pinfunction "A_2") (pintype "passive"))
      (node (ref "R1") (pin "2") (pinfunction "2_2") (pintype "passive"))
    )
    (net (code "43") (name "Net-(S1A-P)") (class "Default")
      (node (ref "R6") (pin "2") (pinfunction "2_2") (pintype "passive"))
      (node (ref "S1") (pin "1A") (pinfunction "P_1A") (pintype "passive"))
    )
    (net (code "44") (name "Net-(S1B-P)") (class "Default")
      (node (ref "R7") (pin "2") (pinfunction "2_2") (pintype "passive"))
      (node (ref "S1") (pin "2A") (pinfunction "P_2A") (pintype "passive"))
    )
    (net (code "45") (name "Net-(S1C-P)") (class "Default")
      (node (ref "R8") (pin "2") (pinfunction "2_2") (pintype "passive"))
      (node (ref "S1") (pin "3A") (pinfunction "P_3A") (pintype "passive"))
    )
    (net (code "46") (name "Net-(S1D-P)") (class "Default")
      (node (ref "R9") (pin "2") (pinfunction "2_2") (pintype "passive"))
      (node (ref "S1") (pin "4A") (pinfunction "P_4A") (pintype "passive"))
    )
    (net (code "47") (name "Net-(S2A-P)") (class "Default")
      (node (ref "R10") (pin "2") (pinfunction "2_2") (pintype "passive"))
      (node (ref "S2") (pin "1A") (pinfunction "P_1A") (pintype "passive"))
    )
    (net (code "48") (name "Net-(S2B-P)") (class "Default")
      (node (ref "R11") (pin "2") (pinfunction "2_2") (pintype "passive"))
      (node (ref "S2") (pin "2A") (pinfunction "P_2A") (pintype "passive"))
    )
    (net (code "49") (name "Net-(S2C-P)") (class "Default")
      (node (ref "R12") (pin "2") (pinfunction "2_2") (pintype "passive"))
      (node (ref "S2") (pin "3A") (pinfunction "P_3A") (pintype "passive"))
    )
    (net (code "50") (name "Net-(S2D-P)") (class "Default")
      (node (ref "R13") (pin "2") (pinfunction "2_2") (pintype "passive"))
      (node (ref "S2") (pin "4A") (pinfunction "P_4A") (pintype "passive"))
    )
    (net (code "51") (name "Net-(S3A-P)") (class "Default")
      (node (ref "R14") (pin "2") (pinfunction "2_2") (pintype "passive"))
      (node (ref "S3") (pin "1A") (pinfunction "P_1A") (pintype "passive"))
    )
    (net (code "52") (name "Net-(S3B-P)") (class "Default")
      (node (ref "R15") (pin "2") (pinfunction "2_2") (pintype "passive"))
      (node (ref "S3") (pin "2A") (pinfunction "P_2A") (pintype "passive"))
    )
    (net (code "53") (name "Net-(S3C-P)") (class "Default")
      (node (ref "R16") (pin "2") (pinfunction "2_2") (pintype "passive"))
      (node (ref "S3") (pin "3A") (pinfunction "P_3A") (pintype "passive"))
    )
    (net (code "54") (name "Net-(S3D-P)") (class "Default")
      (node (ref "R17") (pin "2") (pinfunction "2_2") (pintype "passive"))
      (node (ref "S3") (pin "4A") (pinfunction "P_4A") (pintype "passive"))
    )
    (net (code "55") (name "Net-(S4A-P)") (class "Default")
      (node (ref "R18") (pin "2") (pinfunction "2_2") (pintype "passive"))
      (node (ref "S4") (pin "1A") (pinfunction "P_1A") (pintype "passive"))
    )
    (net (code "56") (name "Net-(S4B-P)") (class "Default")
      (node (ref "R19") (pin "2") (pinfunction "2_2") (pintype "passive"))
      (node (ref "S4") (pin "2A") (pinfunction "P_2A") (pintype "passive"))
    )
    (net (code "57") (name "Net-(S4C-P)") (class "Default")
      (node (ref "R20") (pin "2") (pinfunction "2_2") (pintype "passive"))
      (node (ref "S4") (pin "3A") (pinfunction "P_3A") (pintype "passive"))
    )
    (net (code "58") (name "Net-(S4D-P)") (class "Default")
      (node (ref "R21") (pin "2") (pinfunction "2_2") (pintype "passive"))
      (node (ref "S4") (pin "4A") (pinfunction "P_4A") (pintype "passive"))
    )
    (net (code "59") (name "Net-(S5A-P)") (class "Default")
      (node (ref "R22") (pin "2") (pinfunction "2_2") (pintype "passive"))
      (node (ref "S5") (pin "1A") (pinfunction "P_1A") (pintype "passive"))
    )
    (net (code "60") (name "Net-(S5B-P)") (class "Default")
      (node (ref "R23") (pin "2") (pinfunction "2_2") (pintype "passive"))
      (node (ref "S5") (pin "2A") (pinfunction "P_2A") (pintype "passive"))
    )
    (net (code "61") (name "Net-(S5C-P)") (class "Default")
      (node (ref "R24") (pin "2") (pinfunction "2_2") (pintype "passive"))
      (node (ref "S5") (pin "3A") (pinfunction "P_3A") (pintype "passive"))
    )
    (net (code "62") (name "Net-(S5D-P)") (class "Default")
      (node (ref "R25") (pin "2") (pinfunction "2_2") (pintype "passive"))
      (node (ref "S5") (pin "4A") (pinfunction "P_4A") (pintype "passive"))
    )
    (net (code "63") (name "Net-(S6A-P)") (class "Default")
      (node (ref "R26") (pin "2") (pinfunction "2_2") (pintype "passive"))
      (node (ref "S6") (pin "1A") (pinfunction "P_1A") (pintype "passive"))
    )
    (net (code "64") (name "Net-(S6B-P)") (class "Default")
      (node (ref "R27") (pin "2") (pinfunction "2_2") (pintype "passive"))
      (node (ref "S6") (pin "2A") (pinfunction "P_2A") (pintype "passive"))
    )
    (net (code "65") (name "Net-(S6C-P)") (class "Default")
      (node (ref "R28") (pin "2") (pinfunction "2_2") (pintype "passive"))
      (node (ref "S6") (pin "3A") (pinfunction "P_3A") (pintype "passive"))
    )
    (net (code "66") (name "Net-(S6D-P)") (class "Default")
      (node (ref "R29") (pin "2") (pinfunction "2_2") (pintype "passive"))
      (node (ref "S6") (pin "4A") (pinfunction "P_4A") (pintype "passive"))
    )
    (net (code "67") (name "Net-(S7A-P)") (class "Default")
      (node (ref "R30") (pin "2") (pinfunction "2_2") (pintype "passive"))
      (node (ref "S7") (pin "1A") (pinfunction "P_1A") (pintype "passive"))
    )
    (net (code "68") (name "Net-(S7B-P)") (class "Default")
      (node (ref "R31") (pin "2") (pinfunction "2_2") (pintype "passive"))
      (node (ref "S7") (pin "2A") (pinfunction "P_2A") (pintype "passive"))
    )
    (net (code "69") (name "Net-(S7C-P)") (class "Default")
      (node (ref "R32") (pin "2") (pinfunction "2_2") (pintype "passive"))
      (node (ref "S7") (pin "3A") (pinfunction "P_3A") (pintype "passive"))
    )
    (net (code "70") (name "Net-(S7D-P)") (class "Default")
      (node (ref "R37") (pin "2") (pinfunction "2_2") (pintype "passive"))
      (node (ref "S7") (pin "4A") (pinfunction "P_4A") (pintype "passive"))
    )
    (net (code "71") (name "Net-(S8A-P)") (class "Default")
      (node (ref "R33") (pin "2") (pinfunction "2_2") (pintype "passive"))
      (node (ref "S8") (pin "1A") (pinfunction "P_1A") (pintype "passive"))
    )
    (net (code "72") (name "Net-(S8B-P)") (class "Default")
      (node (ref "R34") (pin "2") (pinfunction "2_2") (pintype "passive"))
      (node (ref "S8") (pin "2A") (pinfunction "P_2A") (pintype "passive"))
    )
    (net (code "73") (name "Net-(S8C-P)") (class "Default")
      (node (ref "R35") (pin "2") (pinfunction "2_2") (pintype "passive"))
      (node (ref "S8") (pin "3A") (pinfunction "P_3A") (pintype "passive"))
    )
    (net (code "74") (name "Net-(S8D-P)") (class "Default")
      (node (ref "R36") (pin "2") (pinfunction "2_2") (pintype "passive"))
      (node (ref "S8") (pin "4A") (pinfunction "P_4A") (pintype "passive"))
    )
    (net (code "75") (name "VBUS") (class "Default")
      (node (ref "C5") (pin "1") (pinfunction "1_1") (pintype "passive"))
      (node (ref "D6") (pin "A") (pinfunction "A_A") (pintype "passive"))
      (node (ref "J12") (pin "A4_B9") (pinfunction "V+_A4_B9") (pintype "power_in"))
      (node (ref "J12") (pin "A9_B4") (pinfunction "V+_A9_B4") (pintype "power_in"))
    )
    (net (code "76") (name "unconnected-(J12-D+-PadA6)") (class "Default")
      (node (ref "J12") (pin "A6") (pinfunction "D+_A6") (pintype "bidirectional"))
    )
    (net (code "77") (name "unconnected-(J12-D+-PadB6)") (class "Default")
      (node (ref "J12") (pin "B6") (pinfunction "D+_B6") (pintype "bidirectional"))
    )
    (net (code "78") (name "unconnected-(J12-D--PadA7)") (class "Default")
      (node (ref "J12") (pin "A7") (pinfunction "D-_A7") (pintype "bidirectional"))
    )
    (net (code "79") (name "unconnected-(J12-D--PadB7)") (class "Default")
      (node (ref "J12") (pin "B7") (pinfunction "D-_B7") (pintype "bidirectional"))
    )
    (net (code "80") (name "unconnected-(J13-S-Pad1)") (class "Default")
      (node (ref "J13") (pin "1") (pinfunction "S_1") (pintype "passive"))
    )
    (net (code "81") (name "unconnected-(J13-SW-Pad4)") (class "Default")
      (node (ref "J13") (pin "4") (pinfunction "SW_4") (pintype "passive"))
    )
    (net (code "82") (name "unconnected-(J14-SW-Pad4)") (class "Default")
      (node (ref "J14") (pin "4") (pinfunction "SW_4") (pintype "passive"))
    )
    (net (code "83") (name "unconnected-(J15-SW-Pad4)") (class "Default")
      (node (ref "J15") (pin "4") (pinfunction "SW_4") (pintype "passive"))
    )
    (net (code "84") (name "unconnected-(J16-SW-Pad4)") (class "Default")
      (node (ref "J16") (pin "4") (pinfunction "SW_4") (pintype "passive"))
    )
    (net (code "85") (name "unconnected-(J17-SW-Pad4)") (class "Default")
      (node (ref "J17") (pin "4") (pinfunction "SW_4") (pintype "passive"))
    )
    (net (code "86") (name "unconnected-(J18-SW-Pad4)") (class "Default")
      (node (ref "J18") (pin "4") (pinfunction "SW_4") (pintype "passive"))
    )
    (net (code "87") (name "unconnected-(J19-SW-Pad4)") (class "Default")
      (node (ref "J19") (pin "4") (pinfunction "SW_4") (pintype "passive"))
    )
    (net (code "88") (name "unconnected-(J20-SW-Pad4)") (class "Default")
      (node (ref "J20") (pin "4") (pinfunction "SW_4") (pintype "passive"))
    )
    (net (code "89") (name "unconnected-(J21-SW-Pad4)") (class "Default")
      (node (ref "J21") (pin "4") (pinfunction "SW_4") (pintype "passive"))
    )
    (net (code "90") (name "unconnected-(J22-SW-Pad4)") (class "Default")
      (node (ref "J22") (pin "4") (pinfunction "SW_4") (pintype "passive"))
    )
    (net (code "91") (name "unconnected-(MP1-PadP$1)") (class "Default")
      (node (ref "MP1") (pin "P$1") (pinfunction "P$1_P$1") (pintype "bidirectional"))
    )
    (net (code "92") (name "unconnected-(MP2-PadP$1)") (class "Default")
      (node (ref "MP2") (pin "P$1") (pinfunction "P$1_P$1") (pintype "bidirectional"))
    )
    (net (code "93") (name "unconnected-(MP3-PadP$1)") (class "Default")
      (node (ref "MP3") (pin "P$1") (pinfunction "P$1_P$1") (pintype "bidirectional"))
    )
    (net (code "94") (name "unconnected-(MP4-PadP$1)") (class "Default")
      (node (ref "MP4") (pin "P$1") (pinfunction "P$1_P$1") (pintype "bidirectional"))
    )
    (net (code "95") (name "unconnected-(OK1-VE-Pad7)") (class "Default")
      (node (ref "OK1") (pin "7") (pinfunction "VE_7") (pintype "passive"))
    )
  )
)
